# DDS_channel.net
KiCad netlist of a schematic drawn in Altium Designer
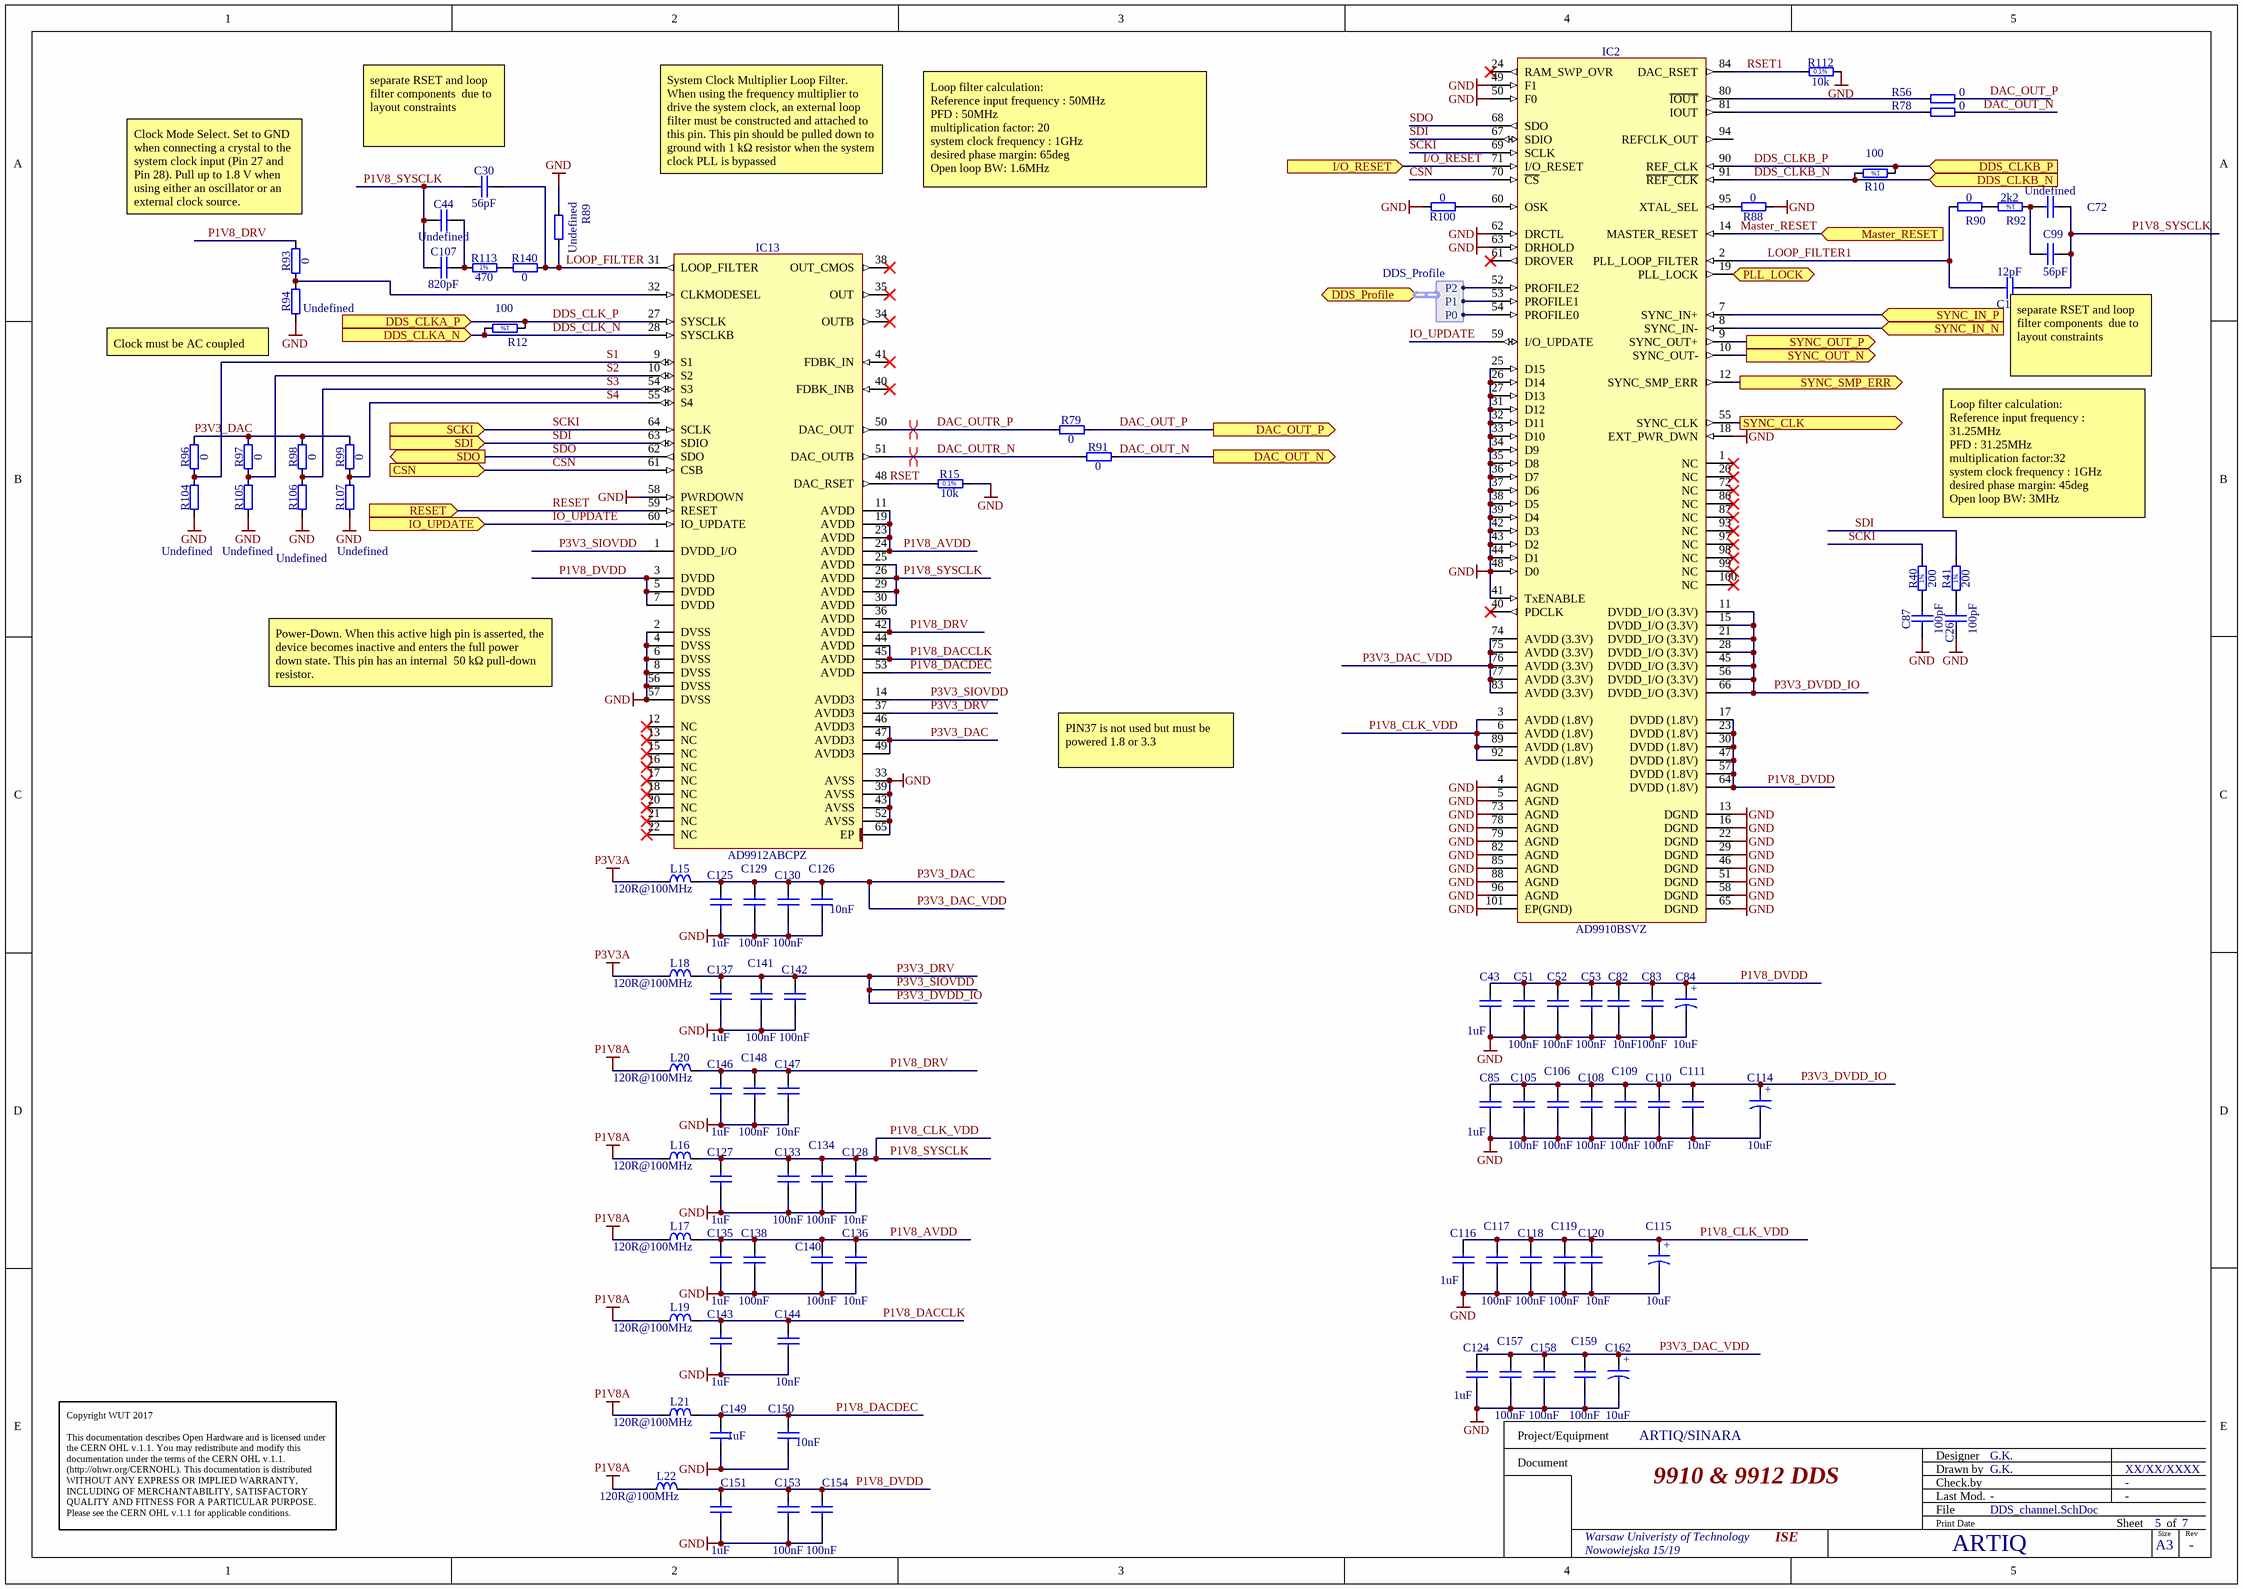
[diagram p0: DDS_channel.SchDoc]

(export (version "E")
  (design (tool "Eeschema 10.0.6"))
  (components
    (comp (ref "C26")
      (value "100pF")
      (footprint "CAPC1005X55N")
      (description "Non-polarised capacitor")
      (fields
        (field (name "PART NUMBER") "CC0402_100PF_50V_5%_C0G")
        (field (name "VOLTAGE") "50V")
        (field (name "AUTHOR") "CERN DEM JLC")
      )
      (libsource (lib "Capacitors") (part "Capacitor - non polarized"))
    )
    (comp (ref "C30")
      (value "56pF")
      (footprint "CAPC1608X87N")
      (description "Non-polarised capacitor")
      (fields
        (field (name "PART NUMBER") "CC0603_56PF_50V_5%_NP0")
        (field (name "VOLTAGE") "50V")
        (field (name "AUTHOR") "CERN DEM JLC")
      )
      (libsource (lib "Capacitors") (part "Capacitor - non polarized"))
    )
    (comp (ref "C43")
      (value "1uF")
      (footprint "CAPC1005X55N")
      (description "Non-polarised capacitor")
      (fields
        (field (name "PART NUMBER") "CC0402_1UF_16V_10%_X5R")
        (field (name "VOLTAGE") "16V")
        (field (name "AUTHOR") "CERN DEM JLC")
      )
      (libsource (lib "Capacitors") (part "Capacitor - non polarized"))
    )
    (comp (ref "C44")
      (value "Undefined")
      (footprint "CAPC1608X90N")
      (description "Non-polarised capacitor")
      (fields (field (name "PART NUMBER") "CC0603_NO-VALUE") (field (name "AUTHOR") "CERN DEM MR"))
      (libsource (lib "Capacitors") (part "Capacitor - non polarized"))
    )
    (comp (ref "C51")
      (value "100nF")
      (footprint "CAPC1005X55N")
      (description "Non-polarised capacitor")
      (fields
        (field (name "PART NUMBER") "CC0402_100NF_16V_10%_X5R")
        (field (name "VOLTAGE") "16V")
        (field (name "AUTHOR") "CERN DEM JLC")
      )
      (libsource (lib "Capacitors") (part "Capacitor - non polarized"))
    )
    (comp (ref "C52")
      (value "100nF")
      (footprint "CAPC1005X55N")
      (description "Non-polarised capacitor")
      (fields
        (field (name "PART NUMBER") "CC0402_100NF_16V_10%_X5R")
        (field (name "VOLTAGE") "16V")
        (field (name "AUTHOR") "CERN DEM JLC")
      )
      (libsource (lib "Capacitors") (part "Capacitor - non polarized"))
    )
    (comp (ref "C53")
      (value "100nF")
      (footprint "CAPC1005X55N")
      (description "Non-polarised capacitor")
      (fields
        (field (name "PART NUMBER") "CC0402_100NF_16V_10%_X5R")
        (field (name "VOLTAGE") "16V")
        (field (name "AUTHOR") "CERN DEM JLC")
      )
      (libsource (lib "Capacitors") (part "Capacitor - non polarized"))
    )
    (comp (ref "C72")
      (value "Undefined")
      (footprint "CAPC1608X90N")
      (description "Non-polarised capacitor")
      (fields (field (name "PART NUMBER") "CC0603_NO-VALUE") (field (name "AUTHOR") "CERN DEM MR"))
      (libsource (lib "Capacitors") (part "Capacitor - non polarized"))
    )
    (comp (ref "C82")
      (value "10nF")
      (footprint "CAPC1005X55N")
      (description "Non-polarised capacitor")
      (fields
        (field (name "PART NUMBER") "CC0402_10NF_16V_10%_X7R")
        (field (name "VOLTAGE") "16V")
        (field (name "AUTHOR") "CERN DEM JLC")
      )
      (libsource (lib "Capacitors") (part "Capacitor - non polarized"))
    )
    (comp (ref "C83")
      (value "100nF")
      (footprint "CAPC1005X55N")
      (description "Non-polarised capacitor")
      (fields
        (field (name "PART NUMBER") "CC0402_100NF_16V_10%_X5R")
        (field (name "VOLTAGE") "16V")
        (field (name "AUTHOR") "CERN DEM JLC")
      )
      (libsource (lib "Capacitors") (part "Capacitor - non polarized"))
    )
    (comp (ref "C84")
      (value "10uF")
      (footprint "CAPMP6032X280N")
      (description "Polarised capacitor")
      (fields
        (field (name "PART NUMBER") "CTE6032-28_10UF_25V_10%_LESR0500")
        (field (name "VOLTAGE") "25V")
        (field (name "AUTHOR") "CERN DEM JLC")
      )
      (libsource (lib "Capacitors") (part "Capacitor - polarized"))
    )
    (comp (ref "C85")
      (value "1uF")
      (footprint "CAPC1005X55N")
      (description "Non-polarised capacitor")
      (fields
        (field (name "PART NUMBER") "CC0402_1UF_16V_10%_X5R")
        (field (name "VOLTAGE") "16V")
        (field (name "AUTHOR") "CERN DEM JLC")
      )
      (libsource (lib "Capacitors") (part "Capacitor - non polarized"))
    )
    (comp (ref "C87")
      (value "100pF")
      (footprint "CAPC1005X55N")
      (description "Non-polarised capacitor")
      (fields
        (field (name "PART NUMBER") "CC0402_100PF_50V_5%_C0G")
        (field (name "VOLTAGE") "50V")
        (field (name "AUTHOR") "CERN DEM JLC")
      )
      (libsource (lib "Capacitors") (part "Capacitor - non polarized"))
    )
    (comp (ref "C99")
      (value "56pF")
      (footprint "CAPC1608X87N")
      (description "Non-polarised capacitor")
      (fields
        (field (name "PART NUMBER") "CC0603_56PF_50V_5%_NP0")
        (field (name "VOLTAGE") "50V")
        (field (name "AUTHOR") "CERN DEM JLC")
      )
      (libsource (lib "Capacitors") (part "Capacitor - non polarized"))
    )
    (comp (ref "C105")
      (value "100nF")
      (footprint "CAPC1005X55N")
      (description "Non-polarised capacitor")
      (fields
        (field (name "PART NUMBER") "CC0402_100NF_16V_10%_X5R")
        (field (name "VOLTAGE") "16V")
        (field (name "AUTHOR") "CERN DEM JLC")
      )
      (libsource (lib "Capacitors") (part "Capacitor - non polarized"))
    )
    (comp (ref "C106")
      (value "100nF")
      (footprint "CAPC1005X55N")
      (description "Non-polarised capacitor")
      (fields
        (field (name "PART NUMBER") "CC0402_100NF_16V_10%_X5R")
        (field (name "VOLTAGE") "16V")
        (field (name "AUTHOR") "CERN DEM JLC")
      )
      (libsource (lib "Capacitors") (part "Capacitor - non polarized"))
    )
    (comp (ref "C107")
      (value "820pF")
      (footprint "CAPC2012X135N")
      (description "Non-polarised capacitor")
      (fields
        (field (name "PART NUMBER") "CC0805_820PF_50V_5%_NP0")
        (field (name "VOLTAGE") "50V")
        (field (name "AUTHOR") "CERN DEM JLC")
      )
      (libsource (lib "Capacitors") (part "Capacitor - non polarized"))
    )
    (comp (ref "C108")
      (value "100nF")
      (footprint "CAPC1005X55N")
      (description "Non-polarised capacitor")
      (fields
        (field (name "PART NUMBER") "CC0402_100NF_16V_10%_X5R")
        (field (name "VOLTAGE") "16V")
        (field (name "AUTHOR") "CERN DEM JLC")
      )
      (libsource (lib "Capacitors") (part "Capacitor - non polarized"))
    )
    (comp (ref "C109")
      (value "100nF")
      (footprint "CAPC1005X55N")
      (description "Non-polarised capacitor")
      (fields
        (field (name "PART NUMBER") "CC0402_100NF_16V_10%_X5R")
        (field (name "VOLTAGE") "16V")
        (field (name "AUTHOR") "CERN DEM JLC")
      )
      (libsource (lib "Capacitors") (part "Capacitor - non polarized"))
    )
    (comp (ref "C110")
      (value "100nF")
      (footprint "CAPC1005X55N")
      (description "Non-polarised capacitor")
      (fields
        (field (name "PART NUMBER") "CC0402_100NF_16V_10%_X5R")
        (field (name "VOLTAGE") "16V")
        (field (name "AUTHOR") "CERN DEM JLC")
      )
      (libsource (lib "Capacitors") (part "Capacitor - non polarized"))
    )
    (comp (ref "C111")
      (value "10nF")
      (footprint "CAPC1005X55N")
      (description "Non-polarised capacitor")
      (fields
        (field (name "PART NUMBER") "CC0402_10NF_16V_10%_X7R")
        (field (name "VOLTAGE") "16V")
        (field (name "AUTHOR") "CERN DEM JLC")
      )
      (libsource (lib "Capacitors") (part "Capacitor - non polarized"))
    )
    (comp (ref "C112")
      (value "12pF")
      (footprint "CAPC1608X87N")
      (description "Non-polarised capacitor")
      (fields
        (field (name "PART NUMBER") "CC0603_12PF_50V_5%_NP0")
        (field (name "VOLTAGE") "50V")
        (field (name "AUTHOR") "CERN DEM JLC")
      )
      (libsource (lib "Capacitors") (part "Capacitor - non polarized"))
    )
    (comp (ref "C114")
      (value "10uF")
      (footprint "CAPMP6032X280N")
      (description "Polarised capacitor")
      (fields
        (field (name "PART NUMBER") "CTE6032-28_10UF_25V_10%_LESR0500")
        (field (name "VOLTAGE") "25V")
        (field (name "AUTHOR") "CERN DEM JLC")
      )
      (libsource (lib "Capacitors") (part "Capacitor - polarized"))
    )
    (comp (ref "C115")
      (value "10uF")
      (footprint "CAPMP6032X280N")
      (description "Polarised capacitor")
      (fields
        (field (name "PART NUMBER") "CTE6032-28_10UF_25V_10%_LESR0500")
        (field (name "VOLTAGE") "25V")
        (field (name "AUTHOR") "CERN DEM JLC")
      )
      (libsource (lib "Capacitors") (part "Capacitor - polarized"))
    )
    (comp (ref "C116")
      (value "1uF")
      (footprint "CAPC1005X55N")
      (description "Non-polarised capacitor")
      (fields
        (field (name "PART NUMBER") "CC0402_1UF_16V_10%_X5R")
        (field (name "VOLTAGE") "16V")
        (field (name "AUTHOR") "CERN DEM JLC")
      )
      (libsource (lib "Capacitors") (part "Capacitor - non polarized"))
    )
    (comp (ref "C117")
      (value "100nF")
      (footprint "CAPC1005X55N")
      (description "Non-polarised capacitor")
      (fields
        (field (name "PART NUMBER") "CC0402_100NF_16V_10%_X5R")
        (field (name "VOLTAGE") "16V")
        (field (name "AUTHOR") "CERN DEM JLC")
      )
      (libsource (lib "Capacitors") (part "Capacitor - non polarized"))
    )
    (comp (ref "C118")
      (value "100nF")
      (footprint "CAPC1005X55N")
      (description "Non-polarised capacitor")
      (fields
        (field (name "PART NUMBER") "CC0402_100NF_16V_10%_X5R")
        (field (name "VOLTAGE") "16V")
        (field (name "AUTHOR") "CERN DEM JLC")
      )
      (libsource (lib "Capacitors") (part "Capacitor - non polarized"))
    )
    (comp (ref "C119")
      (value "100nF")
      (footprint "CAPC1005X55N")
      (description "Non-polarised capacitor")
      (fields
        (field (name "PART NUMBER") "CC0402_100NF_16V_10%_X5R")
        (field (name "VOLTAGE") "16V")
        (field (name "AUTHOR") "CERN DEM JLC")
      )
      (libsource (lib "Capacitors") (part "Capacitor - non polarized"))
    )
    (comp (ref "C120")
      (value "10nF")
      (footprint "CAPC1005X55N")
      (description "Non-polarised capacitor")
      (fields
        (field (name "PART NUMBER") "CC0402_10NF_16V_10%_X7R")
        (field (name "VOLTAGE") "16V")
        (field (name "AUTHOR") "CERN DEM JLC")
      )
      (libsource (lib "Capacitors") (part "Capacitor - non polarized"))
    )
    (comp (ref "C124")
      (value "1uF")
      (footprint "CAPC1005X55N")
      (description "Non-polarised capacitor")
      (fields
        (field (name "PART NUMBER") "CC0402_1UF_16V_10%_X5R")
        (field (name "VOLTAGE") "16V")
        (field (name "AUTHOR") "CERN DEM JLC")
      )
      (libsource (lib "Capacitors") (part "Capacitor - non polarized"))
    )
    (comp (ref "C125")
      (value "1uF")
      (footprint "CAPC1005X55N")
      (description "Non-polarised capacitor")
      (fields
        (field (name "PART NUMBER") "CC0402_1UF_16V_10%_X5R")
        (field (name "VOLTAGE") "16V")
        (field (name "AUTHOR") "CERN DEM JLC")
      )
      (libsource (lib "Capacitors") (part "Capacitor - non polarized"))
    )
    (comp (ref "C126")
      (value "10nF")
      (footprint "CAPC1005X55N")
      (description "Non-polarised capacitor")
      (fields
        (field (name "PART NUMBER") "CC0402_10NF_16V_10%_X7R")
        (field (name "VOLTAGE") "16V")
        (field (name "AUTHOR") "CERN DEM JLC")
      )
      (libsource (lib "Capacitors") (part "Capacitor - non polarized"))
    )
    (comp (ref "C127")
      (value "1uF")
      (footprint "CAPC1005X55N")
      (description "Non-polarised capacitor")
      (fields
        (field (name "PART NUMBER") "CC0402_1UF_16V_10%_X5R")
        (field (name "VOLTAGE") "16V")
        (field (name "AUTHOR") "CERN DEM JLC")
      )
      (libsource (lib "Capacitors") (part "Capacitor - non polarized"))
    )
    (comp (ref "C128")
      (value "10nF")
      (footprint "CAPC1005X55N")
      (description "Non-polarised capacitor")
      (fields
        (field (name "PART NUMBER") "CC0402_10NF_16V_10%_X7R")
        (field (name "VOLTAGE") "16V")
        (field (name "AUTHOR") "CERN DEM JLC")
      )
      (libsource (lib "Capacitors") (part "Capacitor - non polarized"))
    )
    (comp (ref "C129")
      (value "100nF")
      (footprint "CAPC1005X55N")
      (description "Non-polarised capacitor")
      (fields
        (field (name "PART NUMBER") "CC0402_100NF_16V_10%_X5R")
        (field (name "VOLTAGE") "16V")
        (field (name "AUTHOR") "CERN DEM JLC")
      )
      (libsource (lib "Capacitors") (part "Capacitor - non polarized"))
    )
    (comp (ref "C130")
      (value "100nF")
      (footprint "CAPC1005X55N")
      (description "Non-polarised capacitor")
      (fields
        (field (name "PART NUMBER") "CC0402_100NF_16V_10%_X5R")
        (field (name "VOLTAGE") "16V")
        (field (name "AUTHOR") "CERN DEM JLC")
      )
      (libsource (lib "Capacitors") (part "Capacitor - non polarized"))
    )
    (comp (ref "C133")
      (value "100nF")
      (footprint "CAPC1005X55N")
      (description "Non-polarised capacitor")
      (fields
        (field (name "PART NUMBER") "CC0402_100NF_16V_10%_X5R")
        (field (name "VOLTAGE") "16V")
        (field (name "AUTHOR") "CERN DEM JLC")
      )
      (libsource (lib "Capacitors") (part "Capacitor - non polarized"))
    )
    (comp (ref "C134")
      (value "100nF")
      (footprint "CAPC1005X55N")
      (description "Non-polarised capacitor")
      (fields
        (field (name "PART NUMBER") "CC0402_100NF_16V_10%_X5R")
        (field (name "VOLTAGE") "16V")
        (field (name "AUTHOR") "CERN DEM JLC")
      )
      (libsource (lib "Capacitors") (part "Capacitor - non polarized"))
    )
    (comp (ref "C135")
      (value "1uF")
      (footprint "CAPC1005X55N")
      (description "Non-polarised capacitor")
      (fields
        (field (name "PART NUMBER") "CC0402_1UF_16V_10%_X5R")
        (field (name "VOLTAGE") "16V")
        (field (name "AUTHOR") "CERN DEM JLC")
      )
      (libsource (lib "Capacitors") (part "Capacitor - non polarized"))
    )
    (comp (ref "C136")
      (value "10nF")
      (footprint "CAPC1005X55N")
      (description "Non-polarised capacitor")
      (fields
        (field (name "PART NUMBER") "CC0402_10NF_16V_10%_X7R")
        (field (name "VOLTAGE") "16V")
        (field (name "AUTHOR") "CERN DEM JLC")
      )
      (libsource (lib "Capacitors") (part "Capacitor - non polarized"))
    )
    (comp (ref "C137")
      (value "1uF")
      (footprint "CAPC1005X55N")
      (description "Non-polarised capacitor")
      (fields
        (field (name "PART NUMBER") "CC0402_1UF_16V_10%_X5R")
        (field (name "VOLTAGE") "16V")
        (field (name "AUTHOR") "CERN DEM JLC")
      )
      (libsource (lib "Capacitors") (part "Capacitor - non polarized"))
    )
    (comp (ref "C138")
      (value "100nF")
      (footprint "CAPC1005X55N")
      (description "Non-polarised capacitor")
      (fields
        (field (name "PART NUMBER") "CC0402_100NF_16V_10%_X5R")
        (field (name "VOLTAGE") "16V")
        (field (name "AUTHOR") "CERN DEM JLC")
      )
      (libsource (lib "Capacitors") (part "Capacitor - non polarized"))
    )
    (comp (ref "C140")
      (value "100nF")
      (footprint "CAPC1005X55N")
      (description "Non-polarised capacitor")
      (fields
        (field (name "PART NUMBER") "CC0402_100NF_16V_10%_X5R")
        (field (name "VOLTAGE") "16V")
        (field (name "AUTHOR") "CERN DEM JLC")
      )
      (libsource (lib "Capacitors") (part "Capacitor - non polarized"))
    )
    (comp (ref "C141")
      (value "100nF")
      (footprint "CAPC1005X55N")
      (description "Non-polarised capacitor")
      (fields
        (field (name "PART NUMBER") "CC0402_100NF_16V_10%_X5R")
        (field (name "VOLTAGE") "16V")
        (field (name "AUTHOR") "CERN DEM JLC")
      )
      (libsource (lib "Capacitors") (part "Capacitor - non polarized"))
    )
    (comp (ref "C142")
      (value "100nF")
      (footprint "CAPC1005X55N")
      (description "Non-polarised capacitor")
      (fields
        (field (name "PART NUMBER") "CC0402_100NF_16V_10%_X5R")
        (field (name "VOLTAGE") "16V")
        (field (name "AUTHOR") "CERN DEM JLC")
      )
      (libsource (lib "Capacitors") (part "Capacitor - non polarized"))
    )
    (comp (ref "C143")
      (value "1uF")
      (footprint "CAPC1005X55N")
      (description "Non-polarised capacitor")
      (fields
        (field (name "PART NUMBER") "CC0402_1UF_16V_10%_X5R")
        (field (name "VOLTAGE") "16V")
        (field (name "AUTHOR") "CERN DEM JLC")
      )
      (libsource (lib "Capacitors") (part "Capacitor - non polarized"))
    )
    (comp (ref "C144")
      (value "10nF")
      (footprint "CAPC1005X55N")
      (description "Non-polarised capacitor")
      (fields
        (field (name "PART NUMBER") "CC0402_10NF_16V_10%_X7R")
        (field (name "VOLTAGE") "16V")
        (field (name "AUTHOR") "CERN DEM JLC")
      )
      (libsource (lib "Capacitors") (part "Capacitor - non polarized"))
    )
    (comp (ref "C146")
      (value "1uF")
      (footprint "CAPC1005X55N")
      (description "Non-polarised capacitor")
      (fields
        (field (name "PART NUMBER") "CC0402_1UF_16V_10%_X5R")
        (field (name "VOLTAGE") "16V")
        (field (name "AUTHOR") "CERN DEM JLC")
      )
      (libsource (lib "Capacitors") (part "Capacitor - non polarized"))
    )
    (comp (ref "C147")
      (value "10nF")
      (footprint "CAPC1005X55N")
      (description "Non-polarised capacitor")
      (fields
        (field (name "PART NUMBER") "CC0402_10NF_16V_10%_X7R")
        (field (name "VOLTAGE") "16V")
        (field (name "AUTHOR") "CERN DEM JLC")
      )
      (libsource (lib "Capacitors") (part "Capacitor - non polarized"))
    )
    (comp (ref "C148")
      (value "100nF")
      (footprint "CAPC1005X55N")
      (description "Non-polarised capacitor")
      (fields
        (field (name "PART NUMBER") "CC0402_100NF_16V_10%_X5R")
        (field (name "VOLTAGE") "16V")
        (field (name "AUTHOR") "CERN DEM JLC")
      )
      (libsource (lib "Capacitors") (part "Capacitor - non polarized"))
    )
    (comp (ref "C149")
      (value "1uF")
      (footprint "CAPC1005X55N")
      (description "Non-polarised capacitor")
      (fields
        (field (name "PART NUMBER") "CC0402_1UF_16V_10%_X5R")
        (field (name "VOLTAGE") "16V")
        (field (name "AUTHOR") "CERN DEM JLC")
      )
      (libsource (lib "Capacitors") (part "Capacitor - non polarized"))
    )
    (comp (ref "C150")
      (value "10nF")
      (footprint "CAPC1005X55N")
      (description "Non-polarised capacitor")
      (fields
        (field (name "PART NUMBER") "CC0402_10NF_16V_10%_X7R")
        (field (name "VOLTAGE") "16V")
        (field (name "AUTHOR") "CERN DEM JLC")
      )
      (libsource (lib "Capacitors") (part "Capacitor - non polarized"))
    )
    (comp (ref "C151")
      (value "1uF")
      (footprint "CAPC1005X55N")
      (description "Non-polarised capacitor")
      (fields
        (field (name "PART NUMBER") "CC0402_1UF_16V_10%_X5R")
        (field (name "VOLTAGE") "16V")
        (field (name "AUTHOR") "CERN DEM JLC")
      )
      (libsource (lib "Capacitors") (part "Capacitor - non polarized"))
    )
    (comp (ref "C153")
      (value "100nF")
      (footprint "CAPC1005X55N")
      (description "Non-polarised capacitor")
      (fields
        (field (name "PART NUMBER") "CC0402_100NF_16V_10%_X5R")
        (field (name "VOLTAGE") "16V")
        (field (name "AUTHOR") "CERN DEM JLC")
      )
      (libsource (lib "Capacitors") (part "Capacitor - non polarized"))
    )
    (comp (ref "C154")
      (value "100nF")
      (footprint "CAPC1005X55N")
      (description "Non-polarised capacitor")
      (fields
        (field (name "PART NUMBER") "CC0402_100NF_16V_10%_X5R")
        (field (name "VOLTAGE") "16V")
        (field (name "AUTHOR") "CERN DEM JLC")
      )
      (libsource (lib "Capacitors") (part "Capacitor - non polarized"))
    )
    (comp (ref "C157")
      (value "100nF")
      (footprint "CAPC1005X55N")
      (description "Non-polarised capacitor")
      (fields
        (field (name "PART NUMBER") "CC0402_100NF_16V_10%_X5R")
        (field (name "VOLTAGE") "16V")
        (field (name "AUTHOR") "CERN DEM JLC")
      )
      (libsource (lib "Capacitors") (part "Capacitor - non polarized"))
    )
    (comp (ref "C158")
      (value "100nF")
      (footprint "CAPC1005X55N")
      (description "Non-polarised capacitor")
      (fields
        (field (name "PART NUMBER") "CC0402_100NF_16V_10%_X5R")
        (field (name "VOLTAGE") "16V")
        (field (name "AUTHOR") "CERN DEM JLC")
      )
      (libsource (lib "Capacitors") (part "Capacitor - non polarized"))
    )
    (comp (ref "C159")
      (value "100nF")
      (footprint "CAPC1005X55N")
      (description "Non-polarised capacitor")
      (fields
        (field (name "PART NUMBER") "CC0402_100NF_16V_10%_X5R")
        (field (name "VOLTAGE") "16V")
        (field (name "AUTHOR") "CERN DEM JLC")
      )
      (libsource (lib "Capacitors") (part "Capacitor - non polarized"))
    )
    (comp (ref "C162")
      (value "10uF")
      (footprint "CAPMP6032X280N")
      (description "Polarised capacitor")
      (fields
        (field (name "PART NUMBER") "CTE6032-28_10UF_25V_10%_LESR0500")
        (field (name "VOLTAGE") "25V")
        (field (name "AUTHOR") "CERN DEM JLC")
      )
      (libsource (lib "Capacitors") (part "Capacitor - polarized"))
    )
    (comp (ref "IC2")
      (value "AD9910BSVZ")
      (footprint "QFP50P1600X1600X120-101N-S500")
      (description "1 GSPS, 14-Bit, 3.3 V CMOS Direct Digital Synthesizer")
      (fields (field (name "MANUFACTURER") "ANALOG DEVICES") (field (name "AUTHOR") "CERN DEM JLC"))
      (libsource (lib "ICs And Semiconductors") (part "AD9910"))
    )
    (comp (ref "IC13")
      (value "AD9912ABCPZ")
      (footprint "QFN50P900X900X100-65N-S536")
      (description "1 GSPS Direct Digital Synthetizer with 14-Bit DAC")
      (fields (field (name "MANUFACTURER") "ANALOG DEVICES") (field (name "AUTHOR") "CERN DEM JLC"))
      (libsource (lib "ICs And Semiconductors") (part "AD9912"))
    )
    (comp (ref "L15")
      (value "120R@100MHz")
      (footprint "INDC1608X95N")
      (description "Inductor")
      (fields
        (field (name "PART NUMBER") "IND0603_MURATA_BLM18PG121SN1D")
        (field (name "POWER") "2A")
        (field (name "AUTHOR") "CERN DEM BC")
      )
      (libsource (lib "Inductors & Transformers") (part "Inductor"))
    )
    (comp (ref "L16")
      (value "120R@100MHz")
      (footprint "INDC1608X95N")
      (description "Inductor")
      (fields
        (field (name "PART NUMBER") "IND0603_MURATA_BLM18PG121SN1D")
        (field (name "POWER") "2A")
        (field (name "AUTHOR") "CERN DEM BC")
      )
      (libsource (lib "Inductors & Transformers") (part "Inductor"))
    )
    (comp (ref "L17")
      (value "120R@100MHz")
      (footprint "INDC1608X95N")
      (description "Inductor")
      (fields
        (field (name "PART NUMBER") "IND0603_MURATA_BLM18PG121SN1D")
        (field (name "POWER") "2A")
        (field (name "AUTHOR") "CERN DEM BC")
      )
      (libsource (lib "Inductors & Transformers") (part "Inductor"))
    )
    (comp (ref "L18")
      (value "120R@100MHz")
      (footprint "INDC1608X95N")
      (description "Inductor")
      (fields
        (field (name "PART NUMBER") "IND0603_MURATA_BLM18PG121SN1D")
        (field (name "POWER") "2A")
        (field (name "AUTHOR") "CERN DEM BC")
      )
      (libsource (lib "Inductors & Transformers") (part "Inductor"))
    )
    (comp (ref "L19")
      (value "120R@100MHz")
      (footprint "INDC1608X95N")
      (description "Inductor")
      (fields
        (field (name "PART NUMBER") "IND0603_MURATA_BLM18PG121SN1D")
        (field (name "POWER") "2A")
        (field (name "AUTHOR") "CERN DEM BC")
      )
      (libsource (lib "Inductors & Transformers") (part "Inductor"))
    )
    (comp (ref "L20")
      (value "120R@100MHz")
      (footprint "INDC1608X95N")
      (description "Inductor")
      (fields
        (field (name "PART NUMBER") "IND0603_MURATA_BLM18PG121SN1D")
        (field (name "POWER") "2A")
        (field (name "AUTHOR") "CERN DEM BC")
      )
      (libsource (lib "Inductors & Transformers") (part "Inductor"))
    )
    (comp (ref "L21")
      (value "120R@100MHz")
      (footprint "INDC1608X95N")
      (description "Inductor")
      (fields
        (field (name "PART NUMBER") "IND0603_MURATA_BLM18PG121SN1D")
        (field (name "POWER") "2A")
        (field (name "AUTHOR") "CERN DEM BC")
      )
      (libsource (lib "Inductors & Transformers") (part "Inductor"))
    )
    (comp (ref "L22")
      (value "120R@100MHz")
      (footprint "INDC1608X95N")
      (description "Inductor")
      (fields
        (field (name "PART NUMBER") "IND0603_MURATA_BLM18PG121SN1D")
        (field (name "POWER") "2A")
        (field (name "AUTHOR") "CERN DEM BC")
      )
      (libsource (lib "Inductors & Transformers") (part "Inductor"))
    )
    (comp (ref "R10")
      (value "100")
      (footprint "RESC1005X40N")
      (description "Resistor - 1%")
      (fields
        (field (name "PART NUMBER") "R0402_100R_1%_0.0625W_100PPM")
        (field (name "POWER") "0.0625W")
        (field (name "AUTHOR") "CERN DEM JLC")
      )
      (libsource (lib "Resistors") (part "Resistor - 1%"))
    )
    (comp (ref "R12")
      (value "100")
      (footprint "RESC1005X40N")
      (description "Resistor - 1%")
      (fields
        (field (name "PART NUMBER") "R0402_100R_1%_0.0625W_100PPM")
        (field (name "POWER") "0.0625W")
        (field (name "AUTHOR") "CERN DEM JLC")
      )
      (libsource (lib "Resistors") (part "Resistor - 1%"))
    )
    (comp (ref "R15")
      (value "10k")
      (footprint "RESC1005X35N")
      (description "Resistor - 0.1%")
      (fields
        (field (name "PART NUMBER") "R0402_10K_0.1%_0.063W_25PPM")
        (field (name "POWER") "0.063W")
        (field (name "AUTHOR") "CERN DEM JMW")
      )
      (libsource (lib "Resistors") (part "Resistor - 0.1%"))
    )
    (comp (ref "R40")
      (value "200")
      (footprint "RESC1005X40N")
      (description "Resistor - 1%")
      (fields
        (field (name "PART NUMBER") "R0402_200R_1%_0.0625W_100PPM")
        (field (name "POWER") "0.0625W")
        (field (name "AUTHOR") "CERN DEM JLC")
      )
      (libsource (lib "Resistors") (part "Resistor - 1%"))
    )
    (comp (ref "R41")
      (value "200")
      (footprint "RESC1005X40N")
      (description "Resistor - 1%")
      (fields
        (field (name "PART NUMBER") "R0402_200R_1%_0.0625W_100PPM")
        (field (name "POWER") "0.0625W")
        (field (name "AUTHOR") "CERN DEM JLC")
      )
      (libsource (lib "Resistors") (part "Resistor - 1%"))
    )
    (comp (ref "R56")
      (value "0")
      (footprint "RESC1005X40N")
      (description "Resistor")
      (fields
        (field (name "PART NUMBER") "R0402_0R_JUMPER")
        (field (name "MANUFACTURER") "GENERIC")
        (field (name "AUTHOR") "CERN DEM JLC")
      )
      (libsource (lib "Resistors") (part "Resistor"))
    )
    (comp (ref "R78")
      (value "0")
      (footprint "RESC1005X40N")
      (description "Resistor")
      (fields
        (field (name "PART NUMBER") "R0402_0R_JUMPER")
        (field (name "MANUFACTURER") "GENERIC")
        (field (name "AUTHOR") "CERN DEM JLC")
      )
      (libsource (lib "Resistors") (part "Resistor"))
    )
    (comp (ref "R79")
      (value "0")
      (footprint "RESC1005X40N")
      (description "Resistor")
      (fields
        (field (name "PART NUMBER") "R0402_0R_JUMPER")
        (field (name "MANUFACTURER") "GENERIC")
        (field (name "AUTHOR") "CERN DEM JLC")
      )
      (libsource (lib "Resistors") (part "Resistor"))
    )
    (comp (ref "R88")
      (value "0")
      (footprint "RESC1005X40N")
      (description "Resistor")
      (fields
        (field (name "PART NUMBER") "R0402_0R_JUMPER")
        (field (name "MANUFACTURER") "GENERIC")
        (field (name "AUTHOR") "CERN DEM JLC")
      )
      (libsource (lib "Resistors") (part "Resistor"))
    )
    (comp (ref "R89")
      (value "Undefined")
      (footprint "RESC1005X40N")
      (description "Resistor")
      (fields (field (name "PART NUMBER") "R0402_NO-VALUE") (field (name "AUTHOR") "CERN DEM JLC"))
      (libsource (lib "Resistors") (part "Resistor"))
    )
    (comp (ref "R90")
      (value "0")
      (footprint "RESC1608X55N")
      (description "Resistor")
      (fields
        (field (name "PART NUMBER") "R0603_0R_JUMPER")
        (field (name "MANUFACTURER") "GENERIC")
        (field (name "AUTHOR") "CERN DEM JLC")
      )
      (libsource (lib "Resistors") (part "Resistor"))
    )
    (comp (ref "R91")
      (value "0")
      (footprint "RESC1005X40N")
      (description "Resistor")
      (fields
        (field (name "PART NUMBER") "R0402_0R_JUMPER")
        (field (name "MANUFACTURER") "GENERIC")
        (field (name "AUTHOR") "CERN DEM JLC")
      )
      (libsource (lib "Resistors") (part "Resistor"))
    )
    (comp (ref "R92")
      (value "2k2")
      (footprint "RESC1608X55N")
      (description "Resistor - 1%")
      (fields
        (field (name "PART NUMBER") "R0603_2K2_1%_0.1W_100PPM")
        (field (name "POWER") "0.1W")
        (field (name "AUTHOR") "CERN DEM JLC")
      )
      (libsource (lib "Resistors") (part "Resistor - 1%"))
    )
    (comp (ref "R93")
      (value "0")
      (footprint "RESC1005X40N")
      (description "Resistor")
      (fields
        (field (name "PART NUMBER") "R0402_0R_JUMPER")
        (field (name "MANUFACTURER") "GENERIC")
        (field (name "AUTHOR") "CERN DEM JLC")
      )
      (libsource (lib "Resistors") (part "Resistor"))
    )
    (comp (ref "R94")
      (value "Undefined")
      (footprint "RESC1005X40N")
      (description "Resistor")
      (fields (field (name "PART NUMBER") "R0402_NO-VALUE") (field (name "AUTHOR") "CERN DEM JLC"))
      (libsource (lib "Resistors") (part "Resistor"))
    )
    (comp (ref "R96")
      (value "0")
      (footprint "RESC1005X40N")
      (description "Resistor")
      (fields
        (field (name "PART NUMBER") "R0402_0R_JUMPER")
        (field (name "MANUFACTURER") "GENERIC")
        (field (name "AUTHOR") "CERN DEM JLC")
      )
      (libsource (lib "Resistors") (part "Resistor"))
    )
    (comp (ref "R97")
      (value "0")
      (footprint "RESC1005X40N")
      (description "Resistor")
      (fields
        (field (name "PART NUMBER") "R0402_0R_JUMPER")
        (field (name "MANUFACTURER") "GENERIC")
        (field (name "AUTHOR") "CERN DEM JLC")
      )
      (libsource (lib "Resistors") (part "Resistor"))
    )
    (comp (ref "R98")
      (value "0")
      (footprint "RESC1005X40N")
      (description "Resistor")
      (fields
        (field (name "PART NUMBER") "R0402_0R_JUMPER")
        (field (name "MANUFACTURER") "GENERIC")
        (field (name "AUTHOR") "CERN DEM JLC")
      )
      (libsource (lib "Resistors") (part "Resistor"))
    )
    (comp (ref "R99")
      (value "0")
      (footprint "RESC1005X40N")
      (description "Resistor")
      (fields
        (field (name "PART NUMBER") "R0402_0R_JUMPER")
        (field (name "MANUFACTURER") "GENERIC")
        (field (name "AUTHOR") "CERN DEM JLC")
      )
      (libsource (lib "Resistors") (part "Resistor"))
    )
    (comp (ref "R100")
      (value "0")
      (footprint "RESC1005X40N")
      (description "Resistor")
      (fields
        (field (name "PART NUMBER") "R0402_0R_JUMPER")
        (field (name "MANUFACTURER") "GENERIC")
        (field (name "AUTHOR") "CERN DEM JLC")
      )
      (libsource (lib "Resistors") (part "Resistor"))
    )
    (comp (ref "R104")
      (value "Undefined")
      (footprint "RESC1005X40N")
      (description "Resistor")
      (fields (field (name "PART NUMBER") "R0402_NO-VALUE") (field (name "AUTHOR") "CERN DEM JLC"))
      (libsource (lib "Resistors") (part "Resistor"))
    )
    (comp (ref "R105")
      (value "Undefined")
      (footprint "RESC1005X40N")
      (description "Resistor")
      (fields (field (name "PART NUMBER") "R0402_NO-VALUE") (field (name "AUTHOR") "CERN DEM JLC"))
      (libsource (lib "Resistors") (part "Resistor"))
    )
    (comp (ref "R106")
      (value "Undefined")
      (footprint "RESC1005X40N")
      (description "Resistor")
      (fields (field (name "PART NUMBER") "R0402_NO-VALUE") (field (name "AUTHOR") "CERN DEM JLC"))
      (libsource (lib "Resistors") (part "Resistor"))
    )
    (comp (ref "R107")
      (value "Undefined")
      (footprint "RESC1005X40N")
      (description "Resistor")
      (fields (field (name "PART NUMBER") "R0402_NO-VALUE") (field (name "AUTHOR") "CERN DEM JLC"))
      (libsource (lib "Resistors") (part "Resistor"))
    )
    (comp (ref "R112")
      (value "10k")
      (footprint "RESC1005X35N")
      (description "Resistor - 0.1%")
      (fields
        (field (name "PART NUMBER") "R0402_10K_0.1%_0.063W_25PPM")
        (field (name "POWER") "0.063W")
        (field (name "AUTHOR") "CERN DEM JMW")
      )
      (libsource (lib "Resistors") (part "Resistor - 0.1%"))
    )
    (comp (ref "R113")
      (value "470")
      (footprint "RESC1608X55N")
      (description "Resistor - 1%")
      (fields
        (field (name "PART NUMBER") "R0603_470R_1%_0.1W_100PPM")
        (field (name "POWER") "0.1W")
        (field (name "AUTHOR") "CERN DEM JLC")
      )
      (libsource (lib "Resistors") (part "Resistor - 1%"))
    )
    (comp (ref "R140")
      (value "0")
      (footprint "RESC1608X55N")
      (description "Resistor")
      (fields
        (field (name "PART NUMBER") "R0603_0R_JUMPER")
        (field (name "MANUFACTURER") "GENERIC")
        (field (name "AUTHOR") "CERN DEM JLC")
      )
      (libsource (lib "Resistors") (part "Resistor"))
    )
  )
  (nets
    (net (code "2") (name "/CSN") (class "Default")
      (node (ref "IC13") (pin "61") (pinfunction "CSB_61") (pintype "input"))
      (node (ref "IC2") (pin "70") (pinfunction "CS_70") (pintype "input"))
    )
    (net (code "3") (name "/DAC_OUTR_N") (class "Default")
      (node (ref "IC13") (pin "51") (pinfunction "DAC_OUTB_51") (pintype "output"))
      (node (ref "R91") (pin "1") (pinfunction "1_1") (pintype "passive"))
    )
    (net (code "4") (name "/DAC_OUTR_P") (class "Default")
      (node (ref "IC13") (pin "50") (pinfunction "DAC_OUT_50") (pintype "output"))
      (node (ref "R79") (pin "1") (pinfunction "1_1") (pintype "passive"))
    )
    (net (code "5") (name "/DAC_OUT_N") (class "Default")
      (node (ref "R78") (pin "2") (pinfunction "2_2") (pintype "passive"))
      (node (ref "R91") (pin "2") (pinfunction "2_2") (pintype "passive"))
    )
    (net (code "6") (name "/DAC_OUT_P") (class "Default")
      (node (ref "R56") (pin "2") (pinfunction "2_2") (pintype "passive"))
      (node (ref "R79") (pin "2") (pinfunction "2_2") (pintype "passive"))
    )
    (net (code "7") (name "/DDS_CLKB_N") (class "Default")
      (node (ref "IC2") (pin "91") (pinfunction "REF_CLK_91") (pintype "input"))
      (node (ref "R10") (pin "2") (pinfunction "2_2") (pintype "passive"))
    )
    (net (code "8") (name "/DDS_CLKB_P") (class "Default")
      (node (ref "IC2") (pin "90") (pinfunction "REF_CLK_90") (pintype "input"))
      (node (ref "R10") (pin "1") (pinfunction "1_1") (pintype "passive"))
    )
    (net (code "9") (name "/DDS_CLK_N") (class "Default")
      (node (ref "IC13") (pin "28") (pinfunction "SYSCLKB_28") (pintype "input"))
      (node (ref "R12") (pin "2") (pinfunction "2_2") (pintype "passive"))
    )
    (net (code "10") (name "/DDS_CLK_P") (class "Default")
      (node (ref "IC13") (pin "27") (pinfunction "SYSCLK_27") (pintype "input"))
      (node (ref "R12") (pin "1") (pinfunction "1_1") (pintype "passive"))
    )
    (net (code "11") (name "/IO_UPDATE") (class "Default")
      (node (ref "IC13") (pin "60") (pinfunction "IO_UPDATE_60") (pintype "input"))
      (node (ref "IC2") (pin "59") (pinfunction "I/O_UPDATE_59") (pintype "bidirectional"))
    )
    (net (code "12") (name "/I{slash}O_RESET") (class "Default")
      (node (ref "IC2") (pin "71") (pinfunction "I/O_RESET_71") (pintype "input"))
    )
    (net (code "13") (name "/LOOP_FILTER") (class "Default")
      (node (ref "C30") (pin "2") (pinfunction "2_2") (pintype "passive"))
      (node (ref "IC13") (pin "31") (pinfunction "LOOP_FILTER_31") (pintype "output"))
      (node (ref "R140") (pin "2") (pinfunction "2_2") (pintype "passive"))
      (node (ref "R89") (pin "1") (pinfunction "1_1") (pintype "passive"))
    )
    (net (code "14") (name "/LOOP_FILTER1") (class "Default")
      (node (ref "C112") (pin "2") (pinfunction "2_2") (pintype "passive"))
      (node (ref "IC2") (pin "2") (pinfunction "PLL_LOOP_FILTER_2") (pintype "input"))
      (node (ref "R90") (pin "2") (pinfunction "2_2") (pintype "passive"))
    )
    (net (code "15") (name "/Master_RESET") (class "Default")
      (node (ref "IC2") (pin "14") (pinfunction "MASTER_RESET_14") (pintype "input"))
    )
    (net (code "16") (name "/P0") (class "Default")
      (node (ref "IC2") (pin "54") (pinfunction "PROFILE0_54") (pintype "input"))
    )
    (net (code "17") (name "/P1") (class "Default")
      (node (ref "IC2") (pin "53") (pinfunction "PROFILE1_53") (pintype "input"))
    )
    (net (code "18") (name "/P1V8_AVDD") (class "Default")
      (node (ref "C135") (pin "2") (pinfunction "2_2") (pintype "passive"))
      (node (ref "C136") (pin "2") (pinfunction "2_2") (pintype "passive"))
      (node (ref "C138") (pin "2") (pinfunction "2_2") (pintype "passive"))
      (node (ref "C140") (pin "2") (pinfunction "2_2") (pintype "passive"))
      (node (ref "IC13") (pin "11") (pinfunction "AVDD_11") (pintype "power_in"))
      (node (ref "IC13") (pin "19") (pinfunction "AVDD_19") (pintype "power_in"))
      (node (ref "IC13") (pin "23") (pinfunction "AVDD_23") (pintype "power_in"))
      (node (ref "IC13") (pin "24") (pinfunction "AVDD_24") (pintype "power_in"))
      (node (ref "L17") (pin "1") (pinfunction "1_1") (pintype "passive"))
    )
    (net (code "19") (name "/P1V8_CLK_VDD") (class "Default")
      (node (ref "C107") (pin "1") (pinfunction "1_1") (pintype "passive"))
      (node (ref "C112") (pin "1") (pinfunction "1_1") (pintype "passive"))
      (node (ref "C115") (pin "1") (pinfunction "1_1") (pintype "passive"))
      (node (ref "C116") (pin "2") (pinfunction "2_2") (pintype "passive"))
      (node (ref "C117") (pin "2") (pinfunction "2_2") (pintype "passive"))
      (node (ref "C118") (pin "2") (pinfunction "2_2") (pintype "passive"))
      (node (ref "C119") (pin "2") (pinfunction "2_2") (pintype "passive"))
      (node (ref "C120") (pin "2") (pinfunction "2_2") (pintype "passive"))
      (node (ref "C127") (pin "2") (pinfunction "2_2") (pintype "passive"))
      (node (ref "C128") (pin "2") (pinfunction "2_2") (pintype "passive"))
      (node (ref "C133") (pin "2") (pinfunction "2_2") (pintype "passive"))
      (node (ref "C134") (pin "2") (pinfunction "2_2") (pintype "passive"))
      (node (ref "C30") (pin "1") (pinfunction "1_1") (pintype "passive"))
      (node (ref "C44") (pin "1") (pinfunction "1_1") (pintype "passive"))
      (node (ref "C72") (pin "1") (pinfunction "1_1") (pintype "passive"))
      (node (ref "C99") (pin "1") (pinfunction "1_1") (pintype "passive"))
      (node (ref "IC13") (pin "25") (pinfunction "AVDD_25") (pintype "power_in"))
      (node (ref "IC13") (pin "26") (pinfunction "AVDD_26") (pintype "power_in"))
      (node (ref "IC13") (pin "29") (pinfunction "AVDD_29") (pintype "power_in"))
      (node (ref "IC13") (pin "30") (pinfunction "AVDD_30") (pintype "power_in"))
      (node (ref "IC2") (pin "3") (pinfunction "AVDD_(1.8V)_3") (pintype "power_in"))
      (node (ref "IC2") (pin "6") (pinfunction "AVDD_(1.8V)_6") (pintype "power_in"))
      (node (ref "IC2") (pin "89") (pinfunction "AVDD_(1.8V)_89") (pintype "power_in"))
      (node (ref "IC2") (pin "92") (pinfunction "AVDD_(1.8V)_92") (pintype "power_in"))
      (node (ref "L16") (pin "1") (pinfunction "1_1") (pintype "passive"))
    )
    (net (code "20") (name "/P1V8_DACCLK") (class "Default")
      (node (ref "C143") (pin "2") (pinfunction "2_2") (pintype "passive"))
      (node (ref "C144") (pin "2") (pinfunction "2_2") (pintype "passive"))
      (node (ref "IC13") (pin "44") (pinfunction "AVDD_44") (pintype "power_in"))
      (node (ref "IC13") (pin "45") (pinfunction "AVDD_45") (pintype "power_in"))
      (node (ref "L19") (pin "1") (pinfunction "1_1") (pintype "passive"))
    )
    (net (code "21") (name "/P1V8_DACDEC") (class "Default")
      (node (ref "C149") (pin "2") (pinfunction "2_2") (pintype "passive"))
      (node (ref "C150") (pin "2") (pinfunction "2_2") (pintype "passive"))
      (node (ref "IC13") (pin "53") (pinfunction "AVDD_53") (pintype "power_in"))
      (node (ref "L21") (pin "1") (pinfunction "1_1") (pintype "passive"))
    )
    (net (code "22") (name "/P1V8_DRV") (class "Default")
      (node (ref "C146") (pin "2") (pinfunction "2_2") (pintype "passive"))
      (node (ref "C147") (pin "2") (pinfunction "2_2") (pintype "passive"))
      (node (ref "C148") (pin "2") (pinfunction "2_2") (pintype "passive"))
      (node (ref "IC13") (pin "36") (pinfunction "AVDD_36") (pintype "power_in"))
      (node (ref "IC13") (pin "42") (pinfunction "AVDD_42") (pintype "power_in"))
      (node (ref "L20") (pin "1") (pinfunction "1_1") (pintype "passive"))
      (node (ref "R93") (pin "2") (pinfunction "2_2") (pintype "passive"))
    )
    (net (code "23") (name "/P1V8_DVDD") (class "Default")
      (node (ref "C151") (pin "2") (pinfunction "2_2") (pintype "passive"))
      (node (ref "C153") (pin "2") (pinfunction "2_2") (pintype "passive"))
      (node (ref "C154") (pin "2") (pinfunction "2_2") (pintype "passive"))
      (node (ref "C43") (pin "2") (pinfunction "2_2") (pintype "passive"))
      (node (ref "C51") (pin "2") (pinfunction "2_2") (pintype "passive"))
      (node (ref "C52") (pin "2") (pinfunction "2_2") (pintype "passive"))
      (node (ref "C53") (pin "2") (pinfunction "2_2") (pintype "passive"))
      (node (ref "C82") (pin "2") (pinfunction "2_2") (pintype "passive"))
      (node (ref "C83") (pin "2") (pinfunction "2_2") (pintype "passive"))
      (node (ref "C84") (pin "1") (pinfunction "1_1") (pintype "passive"))
      (node (ref "IC13") (pin "3") (pinfunction "DVDD_3") (pintype "power_in"))
      (node (ref "IC13") (pin "5") (pinfunction "DVDD_5") (pintype "power_in"))
      (node (ref "IC13") (pin "7") (pinfunction "DVDD_7") (pintype "power_in"))
      (node (ref "IC2") (pin "17") (pinfunction "DVDD_(1.8V)_17") (pintype "power_in"))
      (node (ref "IC2") (pin "23") (pinfunction "DVDD_(1.8V)_23") (pintype "power_in"))
      (node (ref "IC2") (pin "30") (pinfunction "DVDD_(1.8V)_30") (pintype "power_in"))
      (node (ref "IC2") (pin "47") (pinfunction "DVDD_(1.8V)_47") (pintype "power_in"))
      (node (ref "IC2") (pin "57") (pinfunction "DVDD_(1.8V)_57") (pintype "power_in"))
      (node (ref "IC2") (pin "64") (pinfunction "DVDD_(1.8V)_64") (pintype "power_in"))
      (node (ref "L22") (pin "1") (pinfunction "1_1") (pintype "passive"))
    )
    (net (code "24") (name "/P2") (class "Default")
      (node (ref "IC2") (pin "52") (pinfunction "PROFILE2_52") (pintype "input"))
    )
    (net (code "25") (name "/P3V3_DAC") (class "Default")
      (node (ref "C124") (pin "2") (pinfunction "2_2") (pintype "passive"))
      (node (ref "C125") (pin "2") (pinfunction "2_2") (pintype "passive"))
      (node (ref "C126") (pin "2") (pinfunction "2_2") (pintype "passive"))
      (node (ref "C129") (pin "2") (pinfunction "2_2") (pintype "passive"))
      (node (ref "C130") (pin "2") (pinfunction "2_2") (pintype "passive"))
      (node (ref "C157") (pin "2") (pinfunction "2_2") (pintype "passive"))
      (node (ref "C158") (pin "2") (pinfunction "2_2") (pintype "passive"))
      (node (ref "C159") (pin "2") (pinfunction "2_2") (pintype "passive"))
      (node (ref "C162") (pin "1") (pinfunction "1_1") (pintype "passive"))
      (node (ref "IC13") (pin "46") (pinfunction "AVDD3_46") (pintype "power_in"))
      (node (ref "IC13") (pin "47") (pinfunction "AVDD3_47") (pintype "power_in"))
      (node (ref "IC13") (pin "49") (pinfunction "AVDD3_49") (pintype "power_in"))
      (node (ref "IC2") (pin "74") (pinfunction "AVDD_(3.3V)_74") (pintype "power_in"))
      (node (ref "IC2") (pin "75") (pinfunction "AVDD_(3.3V)_75") (pintype "power_in"))
      (node (ref "IC2") (pin "76") (pinfunction "AVDD_(3.3V)_76") (pintype "power_in"))
      (node (ref "IC2") (pin "77") (pinfunction "AVDD_(3.3V)_77") (pintype "power_in"))
      (node (ref "IC2") (pin "83") (pinfunction "AVDD_(3.3V)_83") (pintype "power_in"))
      (node (ref "L15") (pin "1") (pinfunction "1_1") (pintype "passive"))
      (node (ref "R96") (pin "2") (pinfunction "2_2") (pintype "passive"))
      (node (ref "R97") (pin "2") (pinfunction "2_2") (pintype "passive"))
      (node (ref "R98") (pin "2") (pinfunction "2_2") (pintype "passive"))
      (node (ref "R99") (pin "2") (pinfunction "2_2") (pintype "passive"))
    )
    (net (code "26") (name "/P3V3_DRV") (class "Default")
      (node (ref "C105") (pin "2") (pinfunction "2_2") (pintype "passive"))
      (node (ref "C106") (pin "2") (pinfunction "2_2") (pintype "passive"))
      (node (ref "C108") (pin "2") (pinfunction "2_2") (pintype "passive"))
      (node (ref "C109") (pin "2") (pinfunction "2_2") (pintype "passive"))
      (node (ref "C110") (pin "2") (pinfunction "2_2") (pintype "passive"))
      (node (ref "C111") (pin "2") (pinfunction "2_2") (pintype "passive"))
      (node (ref "C114") (pin "1") (pinfunction "1_1") (pintype "passive"))
      (node (ref "C137") (pin "2") (pinfunction "2_2") (pintype "passive"))
      (node (ref "C141") (pin "2") (pinfunction "2_2") (pintype "passive"))
      (node (ref "C142") (pin "2") (pinfunction "2_2") (pintype "passive"))
      (node (ref "C85") (pin "2") (pinfunction "2_2") (pintype "passive"))
      (node (ref "IC13") (pin "1") (pinfunction "DVDD_I/O_1") (pintype "power_in"))
      (node (ref "IC13") (pin "14") (pinfunction "AVDD3_14") (pintype "power_in"))
      (node (ref "IC13") (pin "37") (pinfunction "AVDD3_37") (pintype "power_in"))
      (node (ref "IC2") (pin "11") (pinfunction "DVDD_I/O_(3.3V)_11") (pintype "power_in"))
      (node (ref "IC2") (pin "15") (pinfunction "DVDD_I/O_(3.3V)_15") (pintype "power_in"))
      (node (ref "IC2") (pin "21") (pinfunction "DVDD_I/O_(3.3V)_21") (pintype "power_in"))
      (node (ref "IC2") (pin "28") (pinfunction "DVDD_I/O_(3.3V)_28") (pintype "power_in"))
      (node (ref "IC2") (pin "45") (pinfunction "DVDD_I/O_(3.3V)_45") (pintype "power_in"))
      (node (ref "IC2") (pin "56") (pinfunction "DVDD_I/O_(3.3V)_56") (pintype "power_in"))
      (node (ref "IC2") (pin "66") (pinfunction "DVDD_I/O_(3.3V)_66") (pintype "power_in"))
      (node (ref "L18") (pin "1") (pinfunction "1_1") (pintype "passive"))
    )
    (net (code "27") (name "/PLL_LOCK") (class "Default")
      (node (ref "IC2") (pin "19") (pinfunction "PLL_LOCK_19") (pintype "output"))
    )
    (net (code "28") (name "/RESET") (class "Default")
      (node (ref "IC13") (pin "59") (pinfunction "RESET_59") (pintype "input"))
    )
    (net (code "29") (name "/RSET") (class "Default")
      (node (ref "IC13") (pin "48") (pinfunction "DAC_RSET_48") (pintype "output"))
      (node (ref "R15") (pin "1") (pinfunction "1_1") (pintype "passive"))
    )
    (net (code "30") (name "/RSET1") (class "Default")
      (node (ref "IC2") (pin "84") (pinfunction "DAC_RSET_84") (pintype "output"))
      (node (ref "R112") (pin "1") (pinfunction "1_1") (pintype "passive"))
    )
    (net (code "31") (name "/S1") (class "Default")
      (node (ref "IC13") (pin "9") (pinfunction "S1_9") (pintype "bidirectional"))
      (node (ref "R104") (pin "2") (pinfunction "2_2") (pintype "passive"))
      (node (ref "R96") (pin "1") (pinfunction "1_1") (pintype "passive"))
    )
    (net (code "32") (name "/S2") (class "Default")
      (node (ref "IC13") (pin "10") (pinfunction "S2_10") (pintype "bidirectional"))
      (node (ref "R105") (pin "2") (pinfunction "2_2") (pintype "passive"))
      (node (ref "R97") (pin "1") (pinfunction "1_1") (pintype "passive"))
    )
    (net (code "33") (name "/S3") (class "Default")
      (node (ref "IC13") (pin "54") (pinfunction "S3_54") (pintype "bidirectional"))
      (node (ref "R106") (pin "2") (pinfunction "2_2") (pintype "passive"))
      (node (ref "R98") (pin "1") (pinfunction "1_1") (pintype "passive"))
    )
    (net (code "34") (name "/S4") (class "Default")
      (node (ref "IC13") (pin "55") (pinfunction "S4_55") (pintype "bidirectional"))
      (node (ref "R107") (pin "2") (pinfunction "2_2") (pintype "passive"))
      (node (ref "R99") (pin "1") (pinfunction "1_1") (pintype "passive"))
    )
    (net (code "35") (name "/SCKI") (class "Default")
      (node (ref "IC13") (pin "64") (pinfunction "SCLK_64") (pintype "input"))
      (node (ref "IC2") (pin "69") (pinfunction "SCLK_69") (pintype "input"))
      (node (ref "R40") (pin "2") (pinfunction "2_2") (pintype "passive"))
    )
    (net (code "36") (name "/SDI") (class "Default")
      (node (ref "IC13") (pin "63") (pinfunction "SDIO_63") (pintype "bidirectional"))
      (node (ref "IC2") (pin "67") (pinfunction "SDIO_67") (pintype "bidirectional"))
      (node (ref "R41") (pin "2") (pinfunction "2_2") (pintype "passive"))
    )
    (net (code "37") (name "/SDO") (class "Default")
      (node (ref "IC13") (pin "62") (pinfunction "SDO_62") (pintype "output"))
      (node (ref "IC2") (pin "68") (pinfunction "SDO_68") (pintype "output"))
    )
    (net (code "38") (name "/SYNC_CLK") (class "Default")
      (node (ref "IC2") (pin "55") (pinfunction "SYNC_CLK_55") (pintype "output"))
    )
    (net (code "39") (name "/SYNC_IN_N") (class "Default")
      (node (ref "IC2") (pin "8") (pinfunction "SYNC_IN-_8") (pintype "input"))
    )
    (net (code "40") (name "/SYNC_IN_P") (class "Default")
      (node (ref "IC2") (pin "7") (pinfunction "SYNC_IN+_7") (pintype "input"))
    )
    (net (code "41") (name "/SYNC_OUT_N") (class "Default")
      (node (ref "IC2") (pin "10") (pinfunction "SYNC_OUT-_10") (pintype "output"))
    )
    (net (code "42") (name "/SYNC_OUT_P") (class "Default")
      (node (ref "IC2") (pin "9") (pinfunction "SYNC_OUT+_9") (pintype "output"))
    )
    (net (code "43") (name "/SYNC_SMP_ERR") (class "Default")
      (node (ref "IC2") (pin "12") (pinfunction "SYNC_SMP_ERR_12") (pintype "output"))
    )
    (net (code "45") (name "GND") (class "Default")
      (node (ref "C105") (pin "1") (pinfunction "1_1") (pintype "passive"))
      (node (ref "C106") (pin "1") (pinfunction "1_1") (pintype "passive"))
      (node (ref "C108") (pin "1") (pinfunction "1_1") (pintype "passive"))
      (node (ref "C109") (pin "1") (pinfunction "1_1") (pintype "passive"))
      (node (ref "C110") (pin "1") (pinfunction "1_1") (pintype "passive"))
      (node (ref "C111") (pin "1") (pinfunction "1_1") (pintype "passive"))
      (node (ref "C114") (pin "2") (pinfunction "2_2") (pintype "passive"))
      (node (ref "C115") (pin "2") (pinfunction "2_2") (pintype "passive"))
      (node (ref "C116") (pin "1") (pinfunction "1_1") (pintype "passive"))
      (node (ref "C117") (pin "1") (pinfunction "1_1") (pintype "passive"))
      (node (ref "C118") (pin "1") (pinfunction "1_1") (pintype "passive"))
      (node (ref "C119") (pin "1") (pinfunction "1_1") (pintype "passive"))
      (node (ref "C120") (pin "1") (pinfunction "1_1") (pintype "passive"))
      (node (ref "C124") (pin "1") (pinfunction "1_1") (pintype "passive"))
      (node (ref "C125") (pin "1") (pinfunction "1_1") (pintype "passive"))
      (node (ref "C126") (pin "1") (pinfunction "1_1") (pintype "passive"))
      (node (ref "C127") (pin "1") (pinfunction "1_1") (pintype "passive"))
      (node (ref "C128") (pin "1") (pinfunction "1_1") (pintype "passive"))
      (node (ref "C129") (pin "1") (pinfunction "1_1") (pintype "passive"))
      (node (ref "C130") (pin "1") (pinfunction "1_1") (pintype "passive"))
      (node (ref "C133") (pin "1") (pinfunction "1_1") (pintype "passive"))
      (node (ref "C134") (pin "1") (pinfunction "1_1") (pintype "passive"))
      (node (ref "C135") (pin "1") (pinfunction "1_1") (pintype "passive"))
      (node (ref "C136") (pin "1") (pinfunction "1_1") (pintype "passive"))
      (node (ref "C137") (pin "1") (pinfunction "1_1") (pintype "passive"))
      (node (ref "C138") (pin "1") (pinfunction "1_1") (pintype "passive"))
      (node (ref "C140") (pin "1") (pinfunction "1_1") (pintype "passive"))
      (node (ref "C141") (pin "1") (pinfunction "1_1") (pintype "passive"))
      (node (ref "C142") (pin "1") (pinfunction "1_1") (pintype "passive"))
      (node (ref "C143") (pin "1") (pinfunction "1_1") (pintype "passive"))
      (node (ref "C144") (pin "1") (pinfunction "1_1") (pintype "passive"))
      (node (ref "C146") (pin "1") (pinfunction "1_1") (pintype "passive"))
      (node (ref "C147") (pin "1") (pinfunction "1_1") (pintype "passive"))
      (node (ref "C148") (pin "1") (pinfunction "1_1") (pintype "passive"))
      (node (ref "C149") (pin "1") (pinfunction "1_1") (pintype "passive"))
      (node (ref "C150") (pin "1") (pinfunction "1_1") (pintype "passive"))
      (node (ref "C151") (pin "1") (pinfunction "1_1") (pintype "passive"))
      (node (ref "C153") (pin "1") (pinfunction "1_1") (pintype "passive"))
      (node (ref "C154") (pin "1") (pinfunction "1_1") (pintype "passive"))
      (node (ref "C157") (pin "1") (pinfunction "1_1") (pintype "passive"))
      (node (ref "C158") (pin "1") (pinfunction "1_1") (pintype "passive"))
      (node (ref "C159") (pin "1") (pinfunction "1_1") (pintype "passive"))
      (node (ref "C162") (pin "2") (pinfunction "2_2") (pintype "passive"))
      (node (ref "C26") (pin "1") (pinfunction "1_1") (pintype "passive"))
      (node (ref "C43") (pin "1") (pinfunction "1_1") (pintype "passive"))
      (node (ref "C51") (pin "1") (pinfunction "1_1") (pintype "passive"))
      (node (ref "C52") (pin "1") (pinfunction "1_1") (pintype "passive"))
      (node (ref "C53") (pin "1") (pinfunction "1_1") (pintype "passive"))
      (node (ref "C82") (pin "1") (pinfunction "1_1") (pintype "passive"))
      (node (ref "C83") (pin "1") (pinfunction "1_1") (pintype "passive"))
      (node (ref "C84") (pin "2") (pinfunction "2_2") (pintype "passive"))
      (node (ref "C85") (pin "1") (pinfunction "1_1") (pintype "passive"))
      (node (ref "C87") (pin "1") (pinfunction "1_1") (pintype "passive"))
      (node (ref "IC13") (pin "2") (pinfunction "DVSS_2") (pintype "power_in"))
      (node (ref "IC13") (pin "33") (pinfunction "AVSS_33") (pintype "power_in"))
      (node (ref "IC13") (pin "39") (pinfunction "AVSS_39") (pintype "power_in"))
      (node (ref "IC13") (pin "4") (pinfunction "DVSS_4") (pintype "power_in"))
      (node (ref "IC13") (pin "43") (pinfunction "AVSS_43") (pintype "power_in"))
      (node (ref "IC13") (pin "52") (pinfunction "AVSS_52") (pintype "power_in"))
      (node (ref "IC13") (pin "56") (pinfunction "DVSS_56") (pintype "power_in"))
      (node (ref "IC13") (pin "57") (pinfunction "DVSS_57") (pintype "power_in"))
      (node (ref "IC13") (pin "58") (pinfunction "PWRDOWN_58") (pintype "input"))
      (node (ref "IC13") (pin "6") (pinfunction "DVSS_6") (pintype "power_in"))
      (node (ref "IC13") (pin "65") (pinfunction "EP_65") (pintype "power_in"))
      (node (ref "IC13") (pin "8") (pinfunction "DVSS_8") (pintype "power_in"))
      (node (ref "IC2") (pin "101") (pinfunction "EP(GND)_101") (pintype "power_in"))
      (node (ref "IC2") (pin "13") (pinfunction "DGND_13") (pintype "power_in"))
      (node (ref "IC2") (pin "16") (pinfunction "DGND_16") (pintype "power_in"))
      (node (ref "IC2") (pin "18") (pinfunction "EXT_PWR_DWN_18") (pintype "input"))
      (node (ref "IC2") (pin "22") (pinfunction "DGND_22") (pintype "power_in"))
      (node (ref "IC2") (pin "25") (pinfunction "D15_25") (pintype "input"))
      (node (ref "IC2") (pin "26") (pinfunction "D14_26") (pintype "input"))
      (node (ref "IC2") (pin "27") (pinfunction "D13_27") (pintype "input"))
      (node (ref "IC2") (pin "29") (pinfunction "DGND_29") (pintype "power_in"))
      (node (ref "IC2") (pin "31") (pinfunction "D12_31") (pintype "input"))
      (node (ref "IC2") (pin "32") (pinfunction "D11_32") (pintype "input"))
      (node (ref "IC2") (pin "33") (pinfunction "D10_33") (pintype "input"))
      (node (ref "IC2") (pin "34") (pinfunction "D9_34") (pintype "input"))
      (node (ref "IC2") (pin "35") (pinfunction "D8_35") (pintype "input"))
      (node (ref "IC2") (pin "36") (pinfunction "D7_36") (pintype "input"))
      (node (ref "IC2") (pin "37") (pinfunction "D6_37") (pintype "input"))
      (node (ref "IC2") (pin "38") (pinfunction "D5_38") (pintype "input"))
      (node (ref "IC2") (pin "39") (pinfunction "D4_39") (pintype "input"))
      (node (ref "IC2") (pin "4") (pinfunction "AGND_4") (pintype "power_in"))
      (node (ref "IC2") (pin "41") (pinfunction "TxENABLE_41") (pintype "input"))
      (node (ref "IC2") (pin "42") (pinfunction "D3_42") (pintype "input"))
      (node (ref "IC2") (pin "43") (pinfunction "D2_43") (pintype "input"))
      (node (ref "IC2") (pin "44") (pinfunction "D1_44") (pintype "input"))
      (node (ref "IC2") (pin "46") (pinfunction "DGND_46") (pintype "power_in"))
      (node (ref "IC2") (pin "48") (pinfunction "D0_48") (pintype "input"))
      (node (ref "IC2") (pin "49") (pinfunction "F1_49") (pintype "input"))
      (node (ref "IC2") (pin "5") (pinfunction "AGND_5") (pintype "power_in"))
      (node (ref "IC2") (pin "50") (pinfunction "F0_50") (pintype "input"))
      (node (ref "IC2") (pin "51") (pinfunction "DGND_51") (pintype "power_in"))
      (node (ref "IC2") (pin "58") (pinfunction "DGND_58") (pintype "power_in"))
      (node (ref "IC2") (pin "62") (pinfunction "DRCTL_62") (pintype "input"))
      (node (ref "IC2") (pin "63") (pinfunction "DRHOLD_63") (pintype "input"))
      (node (ref "IC2") (pin "65") (pinfunction "DGND_65") (pintype "power_in"))
      (node (ref "IC2") (pin "73") (pinfunction "AGND_73") (pintype "power_in"))
      (node (ref "IC2") (pin "78") (pinfunction "AGND_78") (pintype "power_in"))
      (node (ref "IC2") (pin "79") (pinfunction "AGND_79") (pintype "power_in"))
      (node (ref "IC2") (pin "82") (pinfunction "AGND_82") (pintype "power_in"))
      (node (ref "IC2") (pin "85") (pinfunction "AGND_85") (pintype "power_in"))
      (node (ref "IC2") (pin "88") (pinfunction "AGND_88") (pintype "power_in"))
      (node (ref "IC2") (pin "96") (pinfunction "AGND_96") (pintype "power_in"))
      (node (ref "R100") (pin "2") (pinfunction "2_2") (pintype "passive"))
      (node (ref "R104") (pin "1") (pinfunction "1_1") (pintype "passive"))
      (node (ref "R105") (pin "1") (pinfunction "1_1") (pintype "passive"))
      (node (ref "R106") (pin "1") (pinfunction "1_1") (pintype "passive"))
      (node (ref "R107") (pin "1") (pinfunction "1_1") (pintype "passive"))
      (node (ref "R112") (pin "2") (pinfunction "2_2") (pintype "passive"))
      (node (ref "R15") (pin "2") (pinfunction "2_2") (pintype "passive"))
      (node (ref "R88") (pin "1") (pinfunction "1_1") (pintype "passive"))
      (node (ref "R89") (pin "2") (pinfunction "2_2") (pintype "passive"))
      (node (ref "R94") (pin "1") (pinfunction "1_1") (pintype "passive"))
    )
    (net (code "46") (name "Net-(C26-Pad2)") (class "Default")
      (node (ref "C26") (pin "2") (pinfunction "2_2") (pintype "passive"))
      (node (ref "R41") (pin "1") (pinfunction "1_1") (pintype "passive"))
    )
    (net (code "47") (name "Net-(C72-Pad2)") (class "Default")
      (node (ref "C72") (pin "2") (pinfunction "2_2") (pintype "passive"))
      (node (ref "C99") (pin "2") (pinfunction "2_2") (pintype "passive"))
      (node (ref "R92") (pin "1") (pinfunction "1_1") (pintype "passive"))
    )
    (net (code "48") (name "Net-(C87-Pad2)") (class "Default")
      (node (ref "C87") (pin "2") (pinfunction "2_2") (pintype "passive"))
      (node (ref "R40") (pin "1") (pinfunction "1_1") (pintype "passive"))
    )
    (net (code "49") (name "Net-(C107-Pad2)") (class "Default")
      (node (ref "C107") (pin "2") (pinfunction "2_2") (pintype "passive"))
      (node (ref "C44") (pin "2") (pinfunction "2_2") (pintype "passive"))
      (node (ref "R113") (pin "1") (pinfunction "1_1") (pintype "passive"))
    )
    (net (code "50") (name "Net-(IC2-IOUT-Pad80)") (class "Default")
      (node (ref "IC2") (pin "80") (pinfunction "IOUT_80") (pintype "output"))
      (node (ref "R56") (pin "1") (pinfunction "1_1") (pintype "passive"))
    )
    (net (code "51") (name "Net-(IC2-IOUT-Pad81)") (class "Default")
      (node (ref "IC2") (pin "81") (pinfunction "IOUT_81") (pintype "output"))
      (node (ref "R78") (pin "1") (pinfunction "1_1") (pintype "passive"))
    )
    (net (code "52") (name "Net-(IC2-OSK)") (class "Default")
      (node (ref "IC2") (pin "60") (pinfunction "OSK_60") (pintype "input"))
      (node (ref "R100") (pin "1") (pinfunction "1_1") (pintype "passive"))
    )
    (net (code "53") (name "Net-(IC2-XTAL_SEL)") (class "Default")
      (node (ref "IC2") (pin "95") (pinfunction "XTAL_SEL_95") (pintype "input"))
      (node (ref "R88") (pin "2") (pinfunction "2_2") (pintype "passive"))
    )
    (net (code "54") (name "Net-(IC13-CLKMODESEL)") (class "Default")
      (node (ref "IC13") (pin "32") (pinfunction "CLKMODESEL_32") (pintype "input"))
      (node (ref "R93") (pin "1") (pinfunction "1_1") (pintype "passive"))
      (node (ref "R94") (pin "2") (pinfunction "2_2") (pintype "passive"))
    )
    (net (code "55") (name "Net-(R90-Pad1)") (class "Default")
      (node (ref "R90") (pin "1") (pinfunction "1_1") (pintype "passive"))
      (node (ref "R92") (pin "2") (pinfunction "2_2") (pintype "passive"))
    )
    (net (code "56") (name "Net-(R113-Pad2)") (class "Default")
      (node (ref "R113") (pin "2") (pinfunction "2_2") (pintype "passive"))
      (node (ref "R140") (pin "1") (pinfunction "1_1") (pintype "passive"))
    )
    (net (code "57") (name "P1V8A") (class "Default")
      (node (ref "L16") (pin "2") (pinfunction "2_2") (pintype "passive"))
      (node (ref "L17") (pin "2") (pinfunction "2_2") (pintype "passive"))
      (node (ref "L19") (pin "2") (pinfunction "2_2") (pintype "passive"))
      (node (ref "L20") (pin "2") (pinfunction "2_2") (pintype "passive"))
      (node (ref "L21") (pin "2") (pinfunction "2_2") (pintype "passive"))
      (node (ref "L22") (pin "2") (pinfunction "2_2") (pintype "passive"))
    )
    (net (code "58") (name "P3V3A") (class "Default")
      (node (ref "L15") (pin "2") (pinfunction "2_2") (pintype "passive"))
      (node (ref "L18") (pin "2") (pinfunction "2_2") (pintype "passive"))
    )
    (net (code "59") (name "unconnected-(IC2-DROVER-Pad61)") (class "Default")
      (node (ref "IC2") (pin "61") (pinfunction "DROVER_61") (pintype "output+no_connect"))
    )
    (net (code "60") (name "unconnected-(IC2-NC-Pad1)") (class "Default")
      (node (ref "IC2") (pin "1") (pinfunction "NC_1") (pintype "passive+no_connect"))
    )
    (net (code "61") (name "unconnected-(IC2-NC-Pad20)") (class "Default")
      (node (ref "IC2") (pin "20") (pinfunction "NC_20") (pintype "passive+no_connect"))
    )
    (net (code "62") (name "unconnected-(IC2-NC-Pad72)") (class "Default")
      (node (ref "IC2") (pin "72") (pinfunction "NC_72") (pintype "passive+no_connect"))
    )
    (net (code "63") (name "unconnected-(IC2-NC-Pad86)") (class "Default")
      (node (ref "IC2") (pin "86") (pinfunction "NC_86") (pintype "passive+no_connect"))
    )
    (net (code "64") (name "unconnected-(IC2-NC-Pad87)") (class "Default")
      (node (ref "IC2") (pin "87") (pinfunction "NC_87") (pintype "passive+no_connect"))
    )
    (net (code "65") (name "unconnected-(IC2-NC-Pad93)") (class "Default")
      (node (ref "IC2") (pin "93") (pinfunction "NC_93") (pintype "passive+no_connect"))
    )
    (net (code "66") (name "unconnected-(IC2-NC-Pad97)") (class "Default")
      (node (ref "IC2") (pin "97") (pinfunction "NC_97") (pintype "passive+no_connect"))
    )
    (net (code "67") (name "unconnected-(IC2-NC-Pad98)") (class "Default")
      (node (ref "IC2") (pin "98") (pinfunction "NC_98") (pintype "passive+no_connect"))
    )
    (net (code "68") (name "unconnected-(IC2-NC-Pad99)") (class "Default")
      (node (ref "IC2") (pin "99") (pinfunction "NC_99") (pintype "passive+no_connect"))
    )
    (net (code "69") (name "unconnected-(IC2-NC-Pad100)") (class "Default")
      (node (ref "IC2") (pin "100") (pinfunction "NC_100") (pintype "passive+no_connect"))
    )
    (net (code "70") (name "unconnected-(IC2-PDCLK-Pad40)") (class "Default")
      (node (ref "IC2") (pin "40") (pinfunction "PDCLK_40") (pintype "output+no_connect"))
    )
    (net (code "71") (name "unconnected-(IC2-RAM_SWP_OVR-Pad24)") (class "Default")
      (node (ref "IC2") (pin "24") (pinfunction "RAM_SWP_OVR_24") (pintype "output+no_connect"))
    )
    (net (code "72") (name "unconnected-(IC2-REFCLK_OUT-Pad94)") (class "Default")
      (node (ref "IC2") (pin "94") (pinfunction "REFCLK_OUT_94") (pintype "output"))
    )
    (net (code "73") (name "unconnected-(IC13-FDBK_IN-Pad41)") (class "Default")
      (node (ref "IC13") (pin "41") (pinfunction "FDBK_IN_41") (pintype "input+no_connect"))
    )
    (net (code "74") (name "unconnected-(IC13-FDBK_INB-Pad40)") (class "Default")
      (node (ref "IC13") (pin "40") (pinfunction "FDBK_INB_40") (pintype "input+no_connect"))
    )
    (net (code "75") (name "unconnected-(IC13-NC-Pad12)") (class "Default")
      (node (ref "IC13") (pin "12") (pinfunction "NC_12") (pintype "passive+no_connect"))
    )
    (net (code "76") (name "unconnected-(IC13-NC-Pad13)") (class "Default")
      (node (ref "IC13") (pin "13") (pinfunction "NC_13") (pintype "passive+no_connect"))
    )
    (net (code "77") (name "unconnected-(IC13-NC-Pad15)") (class "Default")
      (node (ref "IC13") (pin "15") (pinfunction "NC_15") (pintype "passive+no_connect"))
    )
    (net (code "78") (name "unconnected-(IC13-NC-Pad16)") (class "Default")
      (node (ref "IC13") (pin "16") (pinfunction "NC_16") (pintype "passive+no_connect"))
    )
    (net (code "79") (name "unconnected-(IC13-NC-Pad17)") (class "Default")
      (node (ref "IC13") (pin "17") (pinfunction "NC_17") (pintype "passive+no_connect"))
    )
    (net (code "80") (name "unconnected-(IC13-NC-Pad18)") (class "Default")
      (node (ref "IC13") (pin "18") (pinfunction "NC_18") (pintype "passive+no_connect"))
    )
    (net (code "81") (name "unconnected-(IC13-NC-Pad20)") (class "Default")
      (node (ref "IC13") (pin "20") (pinfunction "NC_20") (pintype "passive+no_connect"))
    )
    (net (code "82") (name "unconnected-(IC13-NC-Pad21)") (class "Default")
      (node (ref "IC13") (pin "21") (pinfunction "NC_21") (pintype "passive+no_connect"))
    )
    (net (code "83") (name "unconnected-(IC13-NC-Pad22)") (class "Default")
      (node (ref "IC13") (pin "22") (pinfunction "NC_22") (pintype "passive+no_connect"))
    )
    (net (code "84") (name "unconnected-(IC13-OUT-Pad35)") (class "Default")
      (node (ref "IC13") (pin "35") (pinfunction "OUT_35") (pintype "output+no_connect"))
    )
    (net (code "85") (name "unconnected-(IC13-OUTB-Pad34)") (class "Default")
      (node (ref "IC13") (pin "34") (pinfunction "OUTB_34") (pintype "output+no_connect"))
    )
    (net (code "86") (name "unconnected-(IC13-OUT_CMOS-Pad38)") (class "Default")
      (node (ref "IC13") (pin "38") (pinfunction "OUT_CMOS_38") (pintype "output+no_connect"))
    )
  )
)
